# ethernet.net
KiCad netlist of a schematic drawn in Altium Designer
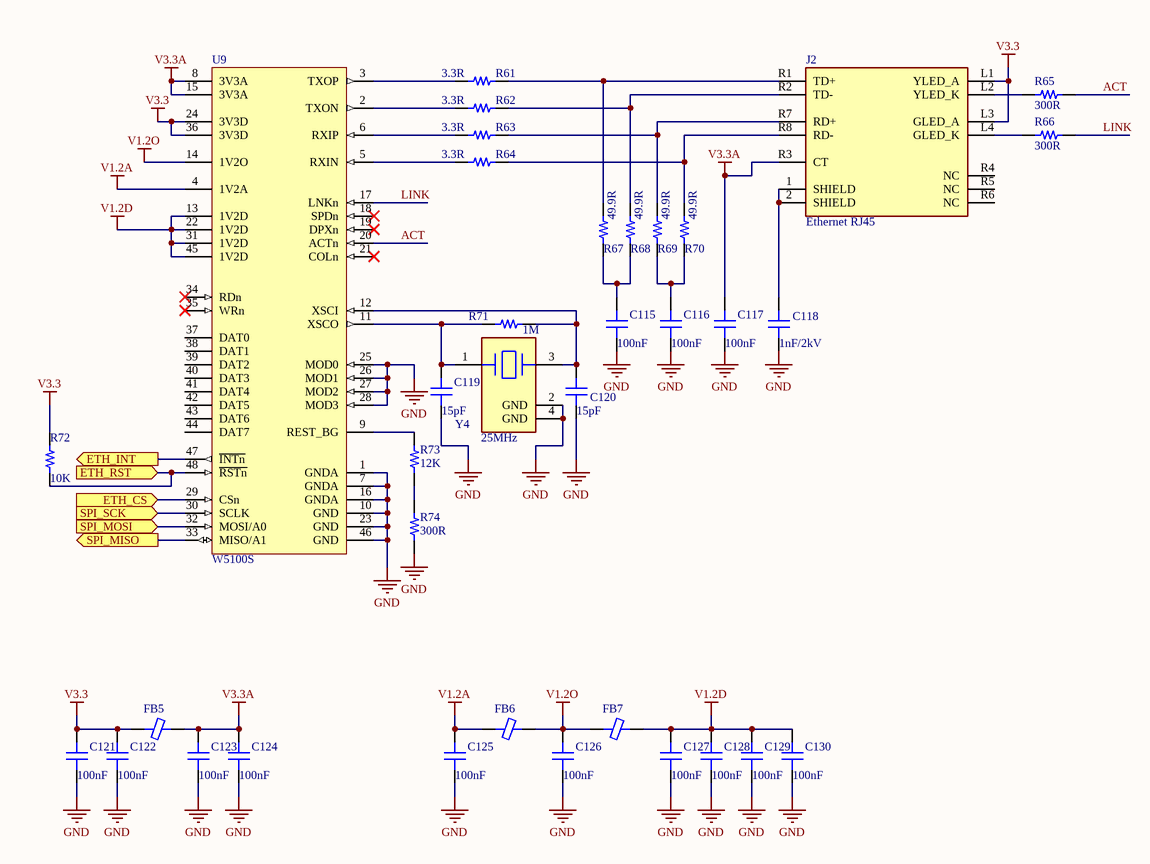
[diagram p0: ethernet.SchDoc]

(export (version "E")
  (design (tool "Eeschema 10.0.6"))
  (components
    (comp (ref "C115")
      (value "100nF")
      (footprint "CAP 0603_1608")
      (description "SMT Capacitor")
      (fields (field (name "MF") "TDK") (field (name "MP") "CGA3E2X7R1E104K080AA"))
      (libsource (lib "Capacitor") (part "Capacitor"))
    )
    (comp (ref "C116")
      (value "100nF")
      (footprint "CAP 0603_1608")
      (description "SMT Capacitor")
      (fields (field (name "MF") "TDK") (field (name "MP") "CGA3E2X7R1E104K080AA"))
      (libsource (lib "Capacitor") (part "Capacitor"))
    )
    (comp (ref "C117")
      (value "100nF")
      (footprint "CAP 0603_1608")
      (description "SMT Capacitor")
      (fields (field (name "MF") "TDK") (field (name "MP") "CGA3E2X7R1E104K080AA"))
      (libsource (lib "Capacitor") (part "Capacitor"))
    )
    (comp (ref "C118")
      (value "1nF/2kV")
      (footprint "CAP 1206_3216")
      (description "SMT Capacitor")
      (fields (field (name "MF") "KEMET") (field (name "MP") "C1206C102KGRAC"))
      (libsource (lib "Capacitor") (part "Capacitor"))
    )
    (comp (ref "C119")
      (value "15pF")
      (footprint "CAP 0603_1608")
      (description "SMT Capacitor")
      (fields (field (name "MF") "Murata") (field (name "MP") "GRM1885C1H150JA01J"))
      (libsource (lib "Capacitor") (part "Capacitor"))
    )
    (comp (ref "C120")
      (value "15pF")
      (footprint "CAP 0603_1608")
      (description "SMT Capacitor")
      (fields (field (name "MF") "Murata") (field (name "MP") "GRM1885C1H150JA01J"))
      (libsource (lib "Capacitor") (part "Capacitor"))
    )
    (comp (ref "C121")
      (value "100nF")
      (footprint "CAP 0603_1608")
      (description "SMT Capacitor")
      (fields (field (name "MF") "TDK") (field (name "MP") "CGA3E2X7R1E104K080AA"))
      (libsource (lib "Capacitor") (part "Capacitor"))
    )
    (comp (ref "C122")
      (value "100nF")
      (footprint "CAP 0603_1608")
      (description "SMT Capacitor")
      (fields (field (name "MF") "TDK") (field (name "MP") "CGA3E2X7R1E104K080AA"))
      (libsource (lib "Capacitor") (part "Capacitor"))
    )
    (comp (ref "C123")
      (value "100nF")
      (footprint "CAP 0603_1608")
      (description "SMT Capacitor")
      (fields (field (name "MF") "TDK") (field (name "MP") "CGA3E2X7R1E104K080AA"))
      (libsource (lib "Capacitor") (part "Capacitor"))
    )
    (comp (ref "C124")
      (value "100nF")
      (footprint "CAP 0603_1608")
      (description "SMT Capacitor")
      (fields (field (name "MF") "TDK") (field (name "MP") "CGA3E2X7R1E104K080AA"))
      (libsource (lib "Capacitor") (part "Capacitor"))
    )
    (comp (ref "C125")
      (value "100nF")
      (footprint "CAP 0603_1608")
      (description "SMT Capacitor")
      (fields (field (name "MF") "TDK") (field (name "MP") "CGA3E2X7R1E104K080AA"))
      (libsource (lib "Capacitor") (part "Capacitor"))
    )
    (comp (ref "C126")
      (value "100nF")
      (footprint "CAP 0603_1608")
      (description "SMT Capacitor")
      (fields (field (name "MF") "TDK") (field (name "MP") "CGA3E2X7R1E104K080AA"))
      (libsource (lib "Capacitor") (part "Capacitor"))
    )
    (comp (ref "C127")
      (value "100nF")
      (footprint "CAP 0603_1608")
      (description "SMT Capacitor")
      (fields (field (name "MF") "TDK") (field (name "MP") "CGA3E2X7R1E104K080AA"))
      (libsource (lib "Capacitor") (part "Capacitor"))
    )
    (comp (ref "C128")
      (value "100nF")
      (footprint "CAP 0603_1608")
      (description "SMT Capacitor")
      (fields (field (name "MF") "TDK") (field (name "MP") "CGA3E2X7R1E104K080AA"))
      (libsource (lib "Capacitor") (part "Capacitor"))
    )
    (comp (ref "C129")
      (value "100nF")
      (footprint "CAP 0603_1608")
      (description "SMT Capacitor")
      (fields (field (name "MF") "TDK") (field (name "MP") "CGA3E2X7R1E104K080AA"))
      (libsource (lib "Capacitor") (part "Capacitor"))
    )
    (comp (ref "C130")
      (value "100nF")
      (footprint "CAP 0603_1608")
      (description "SMT Capacitor")
      (fields (field (name "MF") "TDK") (field (name "MP") "CGA3E2X7R1E104K080AA"))
      (libsource (lib "Capacitor") (part "Capacitor"))
    )
    (comp (ref "FB5")
      (value "Ferrite Beads")
      (footprint "Murata_BLM18-0_15-t0_8_MFG")
      (description "SMT Ferrite Chip")
      (fields (field (name "MF") "TDK") (field (name "MP") "MAF1608GAD601CT000"))
      (libsource (lib "Passive") (part "Ferrite Chip"))
    )
    (comp (ref "FB6")
      (value "Ferrite Beads")
      (footprint "Murata_BLM18-0_15-t0_8_MFG")
      (description "SMT Ferrite Chip")
      (fields (field (name "MF") "TDK") (field (name "MP") "MAF1608GAD601CT000"))
      (libsource (lib "Passive") (part "Ferrite Chip"))
    )
    (comp (ref "FB7")
      (value "Ferrite Beads")
      (footprint "Murata_BLM18-0_15-t0_8_MFG")
      (description "SMT Ferrite Chip")
      (fields (field (name "MF") "TDK") (field (name "MP") "MAF1608GAD601CT000"))
      (libsource (lib "Passive") (part "Ferrite Chip"))
    )
    (comp (ref "J2")
      (value "Ethernet RJ45")
      (footprint "WIZnet_RB1-125BAG1A_0")
      (description "Modular Connectors / Ethernet Connectors RJ-45 w/ Transformer connector/ude")
      (fields (field (name "MF") "WIZnet") (field (name "MP") "RB1-125BAG1A"))
      (libsource (lib "Connector") (part "Ethernet RJ45"))
    )
    (comp (ref "R61")
      (value "3.3R")
      (footprint "RES 0603_1608")
      (description "SMT Resistor")
      (fields (field (name "MF") "YAGEO") (field (name "MP") "AC0603FR-073R3L"))
      (libsource (lib "Resistor") (part "Resistor"))
    )
    (comp (ref "R62")
      (value "3.3R")
      (footprint "RES 0603_1608")
      (description "SMT Resistor")
      (fields (field (name "MF") "YAGEO") (field (name "MP") "AC0603FR-073R3L"))
      (libsource (lib "Resistor") (part "Resistor"))
    )
    (comp (ref "R63")
      (value "3.3R")
      (footprint "RES 0603_1608")
      (description "SMT Resistor")
      (fields (field (name "MF") "YAGEO") (field (name "MP") "AC0603FR-073R3L"))
      (libsource (lib "Resistor") (part "Resistor"))
    )
    (comp (ref "R64")
      (value "3.3R")
      (footprint "RES 0603_1608")
      (description "SMT Resistor")
      (fields (field (name "MF") "YAGEO") (field (name "MP") "AC0603FR-073R3L"))
      (libsource (lib "Resistor") (part "Resistor"))
    )
    (comp (ref "R65")
      (value "300R")
      (footprint "RES 0603_1608")
      (description "SMT Resistor")
      (fields (field (name "MF") "YAGEO") (field (name "MP") "AC0603FR-07300RL"))
      (libsource (lib "Resistor") (part "Resistor"))
    )
    (comp (ref "R66")
      (value "300R")
      (footprint "RES 0603_1608")
      (description "SMT Resistor")
      (fields (field (name "MF") "YAGEO") (field (name "MP") "AC0603FR-07300RL"))
      (libsource (lib "Resistor") (part "Resistor"))
    )
    (comp (ref "R67")
      (value "49.9R")
      (footprint "RES 0603_1608")
      (description "SMT Resistor")
      (fields (field (name "MF") "YAGEO") (field (name "MP") "AC0603FR-0749R9L"))
      (libsource (lib "Resistor") (part "Resistor"))
    )
    (comp (ref "R68")
      (value "49.9R")
      (footprint "RES 0603_1608")
      (description "SMT Resistor")
      (fields (field (name "MF") "YAGEO") (field (name "MP") "AC0603FR-0749R9L"))
      (libsource (lib "Resistor") (part "Resistor"))
    )
    (comp (ref "R69")
      (value "49.9R")
      (footprint "RES 0603_1608")
      (description "SMT Resistor")
      (fields (field (name "MF") "YAGEO") (field (name "MP") "AC0603FR-0749R9L"))
      (libsource (lib "Resistor") (part "Resistor"))
    )
    (comp (ref "R70")
      (value "49.9R")
      (footprint "RES 0603_1608")
      (description "SMT Resistor")
      (fields (field (name "MF") "YAGEO") (field (name "MP") "AC0603FR-0749R9L"))
      (libsource (lib "Resistor") (part "Resistor"))
    )
    (comp (ref "R71")
      (value "1M")
      (footprint "RES 0603_1608")
      (description "SMT Resistor")
      (fields (field (name "MF") "YAGEO") (field (name "MP") "AC0603FR-071ML"))
      (libsource (lib "Resistor") (part "Resistor"))
    )
    (comp (ref "R72")
      (value "10K")
      (footprint "RES 0603_1608")
      (description "SMT Resistor")
      (fields (field (name "MF") "YAGEO") (field (name "MP") "AC0603FR-0710KL"))
      (libsource (lib "Resistor") (part "Resistor"))
    )
    (comp (ref "R73")
      (value "12K")
      (footprint "RES 0603_1608")
      (description "SMT Resistor")
      (fields (field (name "MF") "YAGEO") (field (name "MP") "AC0603FR-0712KL"))
      (libsource (lib "Resistor") (part "Resistor"))
    )
    (comp (ref "R74")
      (value "300R")
      (footprint "RES 0603_1608")
      (description "SMT Resistor")
      (fields (field (name "MF") "YAGEO") (field (name "MP") "AC0603FR-07300RL"))
      (libsource (lib "Resistor") (part "Resistor"))
    )
    (comp (ref "U9")
      (value "W5100S")
      (footprint "WIZ-W5500-LQFP-48_N")
      (description "Ethernet ICs 10/100 Base-T/TX PHY SPI Interface 7x7")
      (fields (field (name "MF") "WIZnet") (field (name "MP") "W5100S-L"))
      (libsource (lib "Ethernet") (part "W5100S"))
    )
    (comp (ref "Y4")
      (value "25MHz")
      (footprint "ABRACON ABM8G")
      (description "Crystals AEC-Q200 CRYSTAL 4pin SMD")
      (fields (field (name "MF") "ECS") (field (name "MP") "ECS-250-12-33-AGN-TR3"))
      (libsource (lib "Crystal") (part "Crystal"))
    )
  )
  (nets
    (net (code "1") (name "/ACT") (class "Default")
      (node (ref "R65") (pin "2") (pinfunction "2_2") (pintype "passive"))
      (node (ref "U9") (pin "20") (pinfunction "ACTn_20") (pintype "input"))
    )
    (net (code "2") (name "/ETH_CS") (class "Default")
      (node (ref "U9") (pin "29") (pinfunction "CSn_29") (pintype "input"))
    )
    (net (code "3") (name "/ETH_INT") (class "Default")
      (node (ref "U9") (pin "47") (pinfunction "~{INTn}_47") (pintype "output"))
    )
    (net (code "4") (name "/ETH_RST") (class "Default")
      (node (ref "R72") (pin "1") (pinfunction "1_1") (pintype "passive"))
      (node (ref "U9") (pin "48") (pinfunction "~{RSTn}_48") (pintype "input"))
    )
    (net (code "5") (name "/LINK") (class "Default")
      (node (ref "R66") (pin "2") (pinfunction "2_2") (pintype "passive"))
      (node (ref "U9") (pin "17") (pinfunction "LNKn_17") (pintype "input"))
    )
    (net (code "6") (name "/SPI_MISO") (class "Default")
      (node (ref "U9") (pin "33") (pinfunction "MISO/A1_33") (pintype "bidirectional"))
    )
    (net (code "7") (name "/SPI_MOSI") (class "Default")
      (node (ref "U9") (pin "32") (pinfunction "MOSI/A0_32") (pintype "input"))
    )
    (net (code "8") (name "/SPI_SCK") (class "Default")
      (node (ref "U9") (pin "30") (pinfunction "SCLK_30") (pintype "input"))
    )
    (net (code "9") (name "GND") (class "Default")
      (node (ref "C115") (pin "2") (pinfunction "2_2") (pintype "passive"))
      (node (ref "C116") (pin "2") (pinfunction "2_2") (pintype "passive"))
      (node (ref "C117") (pin "2") (pinfunction "2_2") (pintype "passive"))
      (node (ref "C118") (pin "1") (pinfunction "1_1") (pintype "passive"))
      (node (ref "C119") (pin "1") (pinfunction "1_1") (pintype "passive"))
      (node (ref "C120") (pin "1") (pinfunction "1_1") (pintype "passive"))
      (node (ref "C121") (pin "2") (pinfunction "2_2") (pintype "passive"))
      (node (ref "C122") (pin "2") (pinfunction "2_2") (pintype "passive"))
      (node (ref "C123") (pin "2") (pinfunction "2_2") (pintype "passive"))
      (node (ref "C124") (pin "2") (pinfunction "2_2") (pintype "passive"))
      (node (ref "C125") (pin "2") (pinfunction "2_2") (pintype "passive"))
      (node (ref "C126") (pin "2") (pinfunction "2_2") (pintype "passive"))
      (node (ref "C127") (pin "2") (pinfunction "2_2") (pintype "passive"))
      (node (ref "C128") (pin "2") (pinfunction "2_2") (pintype "passive"))
      (node (ref "C129") (pin "2") (pinfunction "2_2") (pintype "passive"))
      (node (ref "C130") (pin "2") (pinfunction "2_2") (pintype "passive"))
      (node (ref "R74") (pin "1") (pinfunction "1_1") (pintype "passive"))
      (node (ref "U9") (pin "1") (pinfunction "GNDA_1") (pintype "power_in"))
      (node (ref "U9") (pin "10") (pinfunction "GND_10") (pintype "power_in"))
      (node (ref "U9") (pin "16") (pinfunction "GNDA_16") (pintype "power_in"))
      (node (ref "U9") (pin "23") (pinfunction "GND_23") (pintype "power_in"))
      (node (ref "U9") (pin "25") (pinfunction "MOD0_25") (pintype "input"))
      (node (ref "U9") (pin "26") (pinfunction "MOD1_26") (pintype "input"))
      (node (ref "U9") (pin "27") (pinfunction "MOD2_27") (pintype "input"))
      (node (ref "U9") (pin "28") (pinfunction "MOD3_28") (pintype "input"))
      (node (ref "U9") (pin "46") (pinfunction "GND_46") (pintype "power_in"))
      (node (ref "U9") (pin "7") (pinfunction "GNDA_7") (pintype "power_in"))
      (node (ref "Y4") (pin "2") (pinfunction "GND_2") (pintype "power_in"))
      (node (ref "Y4") (pin "4") (pinfunction "GND_4") (pintype "power_in"))
    )
    (net (code "10") (name "Net-(C115-Pad1)") (class "Default")
      (node (ref "C115") (pin "1") (pinfunction "1_1") (pintype "passive"))
      (node (ref "R67") (pin "1") (pinfunction "1_1") (pintype "passive"))
      (node (ref "R68") (pin "1") (pinfunction "1_1") (pintype "passive"))
    )
    (net (code "11") (name "Net-(C116-Pad1)") (class "Default")
      (node (ref "C116") (pin "1") (pinfunction "1_1") (pintype "passive"))
      (node (ref "R69") (pin "1") (pinfunction "1_1") (pintype "passive"))
      (node (ref "R70") (pin "1") (pinfunction "1_1") (pintype "passive"))
    )
    (net (code "12") (name "Net-(C118-Pad2)") (class "Default")
      (node (ref "C118") (pin "2") (pinfunction "2_2") (pintype "passive"))
      (node (ref "J2") (pin "1") (pinfunction "SHIELD_1") (pintype "passive"))
      (node (ref "J2") (pin "2") (pinfunction "SHIELD_2") (pintype "passive"))
    )
    (net (code "13") (name "Net-(J2-GLED_K)") (class "Default")
      (node (ref "J2") (pin "L4") (pinfunction "GLED_K_L4") (pintype "passive"))
      (node (ref "R66") (pin "1") (pinfunction "1_1") (pintype "passive"))
    )
    (net (code "14") (name "Net-(J2-RD+)") (class "Default")
      (node (ref "J2") (pin "R7") (pinfunction "RD+_R7") (pintype "passive"))
      (node (ref "R63") (pin "2") (pinfunction "2_2") (pintype "passive"))
      (node (ref "R69") (pin "2") (pinfunction "2_2") (pintype "passive"))
    )
    (net (code "15") (name "Net-(J2-RD-)") (class "Default")
      (node (ref "J2") (pin "R8") (pinfunction "RD-_R8") (pintype "passive"))
      (node (ref "R64") (pin "2") (pinfunction "2_2") (pintype "passive"))
      (node (ref "R70") (pin "2") (pinfunction "2_2") (pintype "passive"))
    )
    (net (code "16") (name "Net-(J2-TD+)") (class "Default")
      (node (ref "J2") (pin "R1") (pinfunction "TD+_R1") (pintype "passive"))
      (node (ref "R61") (pin "2") (pinfunction "2_2") (pintype "passive"))
      (node (ref "R67") (pin "2") (pinfunction "2_2") (pintype "passive"))
    )
    (net (code "17") (name "Net-(J2-TD-)") (class "Default")
      (node (ref "J2") (pin "R2") (pinfunction "TD-_R2") (pintype "passive"))
      (node (ref "R62") (pin "2") (pinfunction "2_2") (pintype "passive"))
      (node (ref "R68") (pin "2") (pinfunction "2_2") (pintype "passive"))
    )
    (net (code "18") (name "Net-(J2-YLED_K)") (class "Default")
      (node (ref "J2") (pin "L2") (pinfunction "YLED_K_L2") (pintype "passive"))
      (node (ref "R65") (pin "1") (pinfunction "1_1") (pintype "passive"))
    )
    (net (code "19") (name "Net-(R73-Pad1)") (class "Default")
      (node (ref "R73") (pin "1") (pinfunction "1_1") (pintype "passive"))
      (node (ref "R74") (pin "2") (pinfunction "2_2") (pintype "passive"))
    )
    (net (code "20") (name "Net-(U9-REST_BG)") (class "Default")
      (node (ref "R73") (pin "2") (pinfunction "2_2") (pintype "passive"))
      (node (ref "U9") (pin "9") (pinfunction "REST_BG_9") (pintype "power_in"))
    )
    (net (code "21") (name "Net-(U9-RXIN)") (class "Default")
      (node (ref "R64") (pin "1") (pinfunction "1_1") (pintype "passive"))
      (node (ref "U9") (pin "5") (pinfunction "RXIN_5") (pintype "input"))
    )
    (net (code "22") (name "Net-(U9-RXIP)") (class "Default")
      (node (ref "R63") (pin "1") (pinfunction "1_1") (pintype "passive"))
      (node (ref "U9") (pin "6") (pinfunction "RXIP_6") (pintype "input"))
    )
    (net (code "23") (name "Net-(U9-TXON)") (class "Default")
      (node (ref "R62") (pin "1") (pinfunction "1_1") (pintype "passive"))
      (node (ref "U9") (pin "2") (pinfunction "TXON_2") (pintype "output"))
    )
    (net (code "24") (name "Net-(U9-TXOP)") (class "Default")
      (node (ref "R61") (pin "1") (pinfunction "1_1") (pintype "passive"))
      (node (ref "U9") (pin "3") (pinfunction "TXOP_3") (pintype "output"))
    )
    (net (code "25") (name "Net-(U9-XSCI)") (class "Default")
      (node (ref "C120") (pin "2") (pinfunction "2_2") (pintype "passive"))
      (node (ref "R71") (pin "1") (pinfunction "1_1") (pintype "passive"))
      (node (ref "U9") (pin "12") (pinfunction "XSCI_12") (pintype "input"))
      (node (ref "Y4") (pin "3") (pinfunction "3_3") (pintype "passive"))
    )
    (net (code "26") (name "Net-(U9-XSCO)") (class "Default")
      (node (ref "C119") (pin "2") (pinfunction "2_2") (pintype "passive"))
      (node (ref "R71") (pin "2") (pinfunction "2_2") (pintype "passive"))
      (node (ref "U9") (pin "11") (pinfunction "XSCO_11") (pintype "output"))
      (node (ref "Y4") (pin "1") (pinfunction "1_1") (pintype "passive"))
    )
    (net (code "27") (name "V1.2A") (class "Default")
      (node (ref "C125") (pin "1") (pinfunction "1_1") (pintype "passive"))
      (node (ref "FB6") (pin "1") (pinfunction "1_1") (pintype "passive"))
      (node (ref "U9") (pin "4") (pinfunction "1V2A_4") (pintype "power_in"))
    )
    (net (code "28") (name "V1.2D") (class "Default")
      (node (ref "C127") (pin "1") (pinfunction "1_1") (pintype "passive"))
      (node (ref "C128") (pin "1") (pinfunction "1_1") (pintype "passive"))
      (node (ref "C129") (pin "1") (pinfunction "1_1") (pintype "passive"))
      (node (ref "C130") (pin "1") (pinfunction "1_1") (pintype "passive"))
      (node (ref "FB7") (pin "2") (pinfunction "2_2") (pintype "passive"))
      (node (ref "U9") (pin "13") (pinfunction "1V2D_13") (pintype "power_in"))
      (node (ref "U9") (pin "22") (pinfunction "1V2D_22") (pintype "power_in"))
      (node (ref "U9") (pin "31") (pinfunction "1V2D_31") (pintype "power_in"))
      (node (ref "U9") (pin "45") (pinfunction "1V2D_45") (pintype "power_in"))
    )
    (net (code "29") (name "V1.2O") (class "Default")
      (node (ref "C126") (pin "1") (pinfunction "1_1") (pintype "passive"))
      (node (ref "FB6") (pin "2") (pinfunction "2_2") (pintype "passive"))
      (node (ref "FB7") (pin "1") (pinfunction "1_1") (pintype "passive"))
      (node (ref "U9") (pin "14") (pinfunction "1V2O_14") (pintype "power_in"))
    )
    (net (code "30") (name "V3.3") (class "Default")
      (node (ref "C121") (pin "1") (pinfunction "1_1") (pintype "passive"))
      (node (ref "C122") (pin "1") (pinfunction "1_1") (pintype "passive"))
      (node (ref "FB5") (pin "1") (pinfunction "1_1") (pintype "passive"))
      (node (ref "J2") (pin "L1") (pinfunction "YLED_A_L1") (pintype "passive"))
      (node (ref "J2") (pin "L3") (pinfunction "GLED_A_L3") (pintype "passive"))
      (node (ref "R72") (pin "2") (pinfunction "2_2") (pintype "passive"))
      (node (ref "U9") (pin "24") (pinfunction "3V3D_24") (pintype "passive"))
      (node (ref "U9") (pin "36") (pinfunction "3V3D_36") (pintype "passive"))
    )
    (net (code "31") (name "V3.3A") (class "Default")
      (node (ref "C117") (pin "1") (pinfunction "1_1") (pintype "passive"))
      (node (ref "C123") (pin "1") (pinfunction "1_1") (pintype "passive"))
      (node (ref "C124") (pin "1") (pinfunction "1_1") (pintype "passive"))
      (node (ref "FB5") (pin "2") (pinfunction "2_2") (pintype "passive"))
      (node (ref "J2") (pin "R3") (pinfunction "CT_R3") (pintype "passive"))
      (node (ref "U9") (pin "15") (pinfunction "3V3A_15") (pintype "passive"))
      (node (ref "U9") (pin "8") (pinfunction "3V3A_8") (pintype "power_in"))
    )
    (net (code "32") (name "unconnected-(J2-NC-PadR4)") (class "Default")
      (node (ref "J2") (pin "R4") (pinfunction "NC_R4") (pintype "passive"))
    )
    (net (code "33") (name "unconnected-(J2-NC-PadR5)") (class "Default")
      (node (ref "J2") (pin "R5") (pinfunction "NC_R5") (pintype "passive"))
    )
    (net (code "34") (name "unconnected-(J2-NC-PadR6)") (class "Default")
      (node (ref "J2") (pin "R6") (pinfunction "NC_R6") (pintype "passive"))
    )
    (net (code "35") (name "unconnected-(U9-COLn-Pad21)") (class "Default")
      (node (ref "U9") (pin "21") (pinfunction "COLn_21") (pintype "input+no_connect"))
    )
    (net (code "36") (name "unconnected-(U9-DAT0-Pad37)") (class "Default")
      (node (ref "U9") (pin "37") (pinfunction "DAT0_37") (pintype "passive"))
    )
    (net (code "37") (name "unconnected-(U9-DAT1-Pad38)") (class "Default")
      (node (ref "U9") (pin "38") (pinfunction "DAT1_38") (pintype "passive"))
    )
    (net (code "38") (name "unconnected-(U9-DAT2-Pad39)") (class "Default")
      (node (ref "U9") (pin "39") (pinfunction "DAT2_39") (pintype "passive"))
    )
    (net (code "39") (name "unconnected-(U9-DAT3-Pad40)") (class "Default")
      (node (ref "U9") (pin "40") (pinfunction "DAT3_40") (pintype "passive"))
    )
    (net (code "40") (name "unconnected-(U9-DAT4-Pad41)") (class "Default")
      (node (ref "U9") (pin "41") (pinfunction "DAT4_41") (pintype "passive"))
    )
    (net (code "41") (name "unconnected-(U9-DAT5-Pad42)") (class "Default")
      (node (ref "U9") (pin "42") (pinfunction "DAT5_42") (pintype "passive"))
    )
    (net (code "42") (name "unconnected-(U9-DAT6-Pad43)") (class "Default")
      (node (ref "U9") (pin "43") (pinfunction "DAT6_43") (pintype "passive"))
    )
    (net (code "43") (name "unconnected-(U9-DAT7-Pad44)") (class "Default")
      (node (ref "U9") (pin "44") (pinfunction "DAT7_44") (pintype "passive"))
    )
    (net (code "44") (name "unconnected-(U9-DPXn-Pad19)") (class "Default")
      (node (ref "U9") (pin "19") (pinfunction "DPXn_19") (pintype "input+no_connect"))
    )
    (net (code "45") (name "unconnected-(U9-RDn-Pad34)") (class "Default")
      (node (ref "U9") (pin "34") (pinfunction "RDn_34") (pintype "input+no_connect"))
    )
    (net (code "46") (name "unconnected-(U9-SPDn-Pad18)") (class "Default")
      (node (ref "U9") (pin "18") (pinfunction "SPDn_18") (pintype "input+no_connect"))
    )
    (net (code "47") (name "unconnected-(U9-WRn-Pad35)") (class "Default")
      (node (ref "U9") (pin "35") (pinfunction "WRn_35") (pintype "input+no_connect"))
    )
  )
)
